# PSU_Schematic.net
KiCad netlist of a schematic drawn in Altium Designer
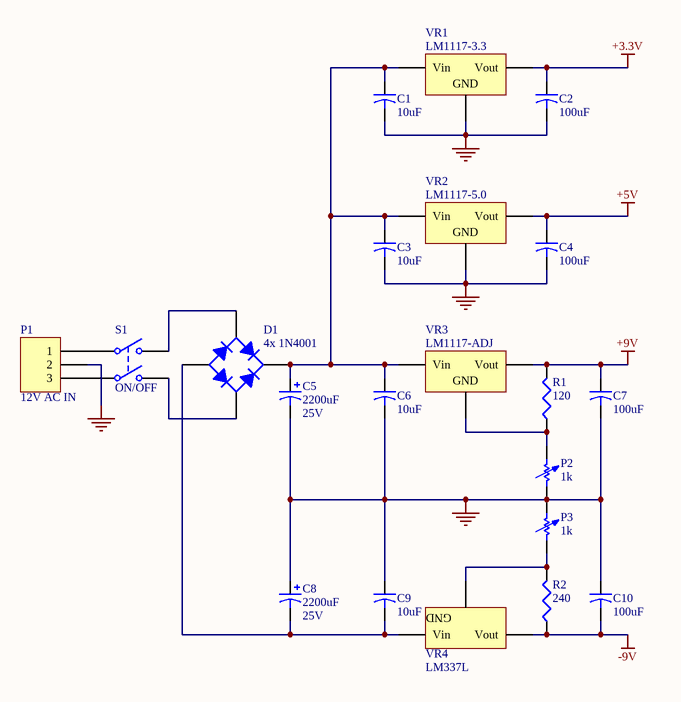
[diagram p0: PSU.Schematic.SchDoc]

(export (version "E")
  (design (tool "Eeschema 10.0.6"))
  (components
    (comp (ref "C1")
      (value "10uF")
      (footprint "CAPR5-4X5")
      (description "Capacitor")
      (fields (field (name "PUBLISHER") "Altium Limited"))
      (libsource (lib "Miscellaneous Devices") (part "Cap2"))
    )
    (comp (ref "C2")
      (value "100uF")
      (footprint "CAPR5-4X5")
      (description "Capacitor")
      (fields (field (name "PUBLISHER") "Altium Limited"))
      (libsource (lib "Miscellaneous Devices") (part "Cap2"))
    )
    (comp (ref "C3")
      (value "10uF")
      (footprint "CAPR5-4X5")
      (description "Capacitor")
      (fields (field (name "PUBLISHER") "Altium Limited"))
      (libsource (lib "Miscellaneous Devices") (part "Cap2"))
    )
    (comp (ref "C4")
      (value "100uF")
      (footprint "CAPR5-4X5")
      (description "Capacitor")
      (fields (field (name "PUBLISHER") "Altium Limited"))
      (libsource (lib "Miscellaneous Devices") (part "Cap2"))
    )
    (comp (ref "C5")
      (value "2200uF")
      (footprint "RB7.6-15")
      (description "Polarized Capacitor (Radial)")
      (fields (field (name "ALTIUM_VALUE") "25V") (field (name "PUBLISHER") "Altium Limited"))
      (libsource (lib "Miscellaneous Devices") (part "Cap Pol1"))
    )
    (comp (ref "C6")
      (value "10uF")
      (footprint "CAPR5-4X5")
      (description "Capacitor")
      (fields (field (name "PUBLISHER") "Altium Limited"))
      (libsource (lib "Miscellaneous Devices") (part "Cap2"))
    )
    (comp (ref "C7")
      (value "100uF")
      (footprint "CAPR5-4X5")
      (description "Capacitor")
      (fields (field (name "PUBLISHER") "Altium Limited"))
      (libsource (lib "Miscellaneous Devices") (part "Cap2"))
    )
    (comp (ref "C8")
      (value "2200uF")
      (footprint "RB7.6-15")
      (description "Polarized Capacitor (Radial)")
      (fields (field (name "ALTIUM_VALUE") "25V") (field (name "PUBLISHER") "Altium Limited"))
      (libsource (lib "Miscellaneous Devices") (part "Cap Pol1"))
    )
    (comp (ref "C9")
      (value "10uF")
      (footprint "CAPR5-4X5")
      (description "Capacitor")
      (fields (field (name "PUBLISHER") "Altium Limited"))
      (libsource (lib "Miscellaneous Devices") (part "Cap2"))
    )
    (comp (ref "C10")
      (value "100uF")
      (footprint "CAPR5-4X5")
      (description "Capacitor")
      (fields (field (name "PUBLISHER") "Altium Limited"))
      (libsource (lib "Miscellaneous Devices") (part "Cap2"))
    )
    (comp (ref "D1")
      (value "4x 1N4001")
      (footprint "D-38")
      (description "Full Wave Diode Bridge")
      (fields (field (name "PUBLISHER") "Altium Limited"))
      (libsource (lib "Miscellaneous Devices") (part "Bridge1"))
    )
    (comp (ref "P1")
      (value "12V AC IN")
      (footprint "HDR1X3")
      (description "Header, 3-Pin")
      (fields (field (name "PUBLISHER") "Altium Limited"))
      (libsource (lib "Miscellaneous Connectors") (part "Header 3"))
    )
    (comp (ref "P2")
      (value "1k")
      (footprint "AXIAL-0.7")
      (description "Variable Resistor")
      (fields (field (name "PUBLISHER") "Altium Limited"))
      (libsource (lib "Miscellaneous Devices") (part "Res Adj1"))
    )
    (comp (ref "P3")
      (value "1k")
      (footprint "AXIAL-0.7")
      (description "Variable Resistor")
      (fields (field (name "PUBLISHER") "Altium Limited"))
      (libsource (lib "Miscellaneous Devices") (part "Res Adj1"))
    )
    (comp (ref "R1")
      (value "120")
      (footprint "J1-0603")
      (description "Resistor")
      (fields (field (name "PUBLISHER") "Altium Limited"))
      (libsource (lib "Miscellaneous Devices") (part "Res3"))
    )
    (comp (ref "R2")
      (value "240")
      (footprint "J1-0603")
      (description "Resistor")
      (fields (field (name "PUBLISHER") "Altium Limited"))
      (libsource (lib "Miscellaneous Devices") (part "Res3"))
    )
    (comp (ref "S1")
      (value "ON/OFF")
      (footprint "DPST-4")
      (description "Double-Pole, Single-Throw Switch")
      (fields (field (name "PUBLISHER") "Altium Limited"))
      (libsource (lib "Miscellaneous Devices") (part "SW-DPST"))
    )
    (comp (ref "VR1")
      (value "LM1117-3.3")
      (footprint "D2PAK_N")
      (description "Voltage Regulator")
      (fields (field (name "PUBLISHER") "Altium Limited"))
      (libsource (lib "") (part "Volt Reg_1"))
    )
    (comp (ref "VR2")
      (value "LM1117-5.0")
      (footprint "D2PAK_N")
      (description "Voltage Regulator")
      (fields (field (name "PUBLISHER") "Altium Limited"))
      (libsource (lib "") (part "Volt Reg_1"))
    )
    (comp (ref "VR3")
      (value "LM1117-ADJ")
      (footprint "D2PAK_N")
      (description "Voltage Regulator")
      (fields (field (name "PUBLISHER") "Altium Limited"))
      (libsource (lib "") (part "Volt Reg_1"))
    )
    (comp (ref "VR4")
      (value "LM337L")
      (footprint "D2PAK_N")
      (description "Voltage Regulator")
      (fields (field (name "PUBLISHER") "Altium Limited"))
      (libsource (lib "Miscellaneous Devices") (part "Volt Reg"))
    )
  )
  (nets
    (net (code "1") (name "+3.3V") (class "Default")
      (node (ref "C2") (pin "1") (pinfunction "1_1") (pintype "passive"))
      (node (ref "VR1") (pin "3") (pinfunction "Vout_3") (pintype "passive"))
    )
    (net (code "2") (name "+5V") (class "Default")
      (node (ref "C4") (pin "1") (pinfunction "1_1") (pintype "passive"))
      (node (ref "VR2") (pin "3") (pinfunction "Vout_3") (pintype "passive"))
    )
    (net (code "3") (name "+9V") (class "Default")
      (node (ref "C7") (pin "1") (pinfunction "1_1") (pintype "passive"))
      (node (ref "R1") (pin "2") (pinfunction "2_2") (pintype "passive"))
      (node (ref "VR3") (pin "3") (pinfunction "Vout_3") (pintype "passive"))
    )
    (net (code "4") (name "-9V") (class "Default")
      (node (ref "C10") (pin "2") (pinfunction "2_2") (pintype "passive"))
      (node (ref "R2") (pin "1") (pinfunction "1_1") (pintype "passive"))
      (node (ref "VR4") (pin "3") (pinfunction "Vout_3") (pintype "passive"))
    )
    (net (code "5") (name "GND") (class "Default")
      (node (ref "C1") (pin "2") (pinfunction "2_2") (pintype "passive"))
      (node (ref "C10") (pin "1") (pinfunction "1_1") (pintype "passive"))
      (node (ref "C2") (pin "2") (pinfunction "2_2") (pintype "passive"))
      (node (ref "C3") (pin "2") (pinfunction "2_2") (pintype "passive"))
      (node (ref "C4") (pin "2") (pinfunction "2_2") (pintype "passive"))
      (node (ref "C5") (pin "2") (pinfunction "2_2") (pintype "passive"))
      (node (ref "C6") (pin "2") (pinfunction "2_2") (pintype "passive"))
      (node (ref "C7") (pin "2") (pinfunction "2_2") (pintype "passive"))
      (node (ref "C8") (pin "1") (pinfunction "1_1") (pintype "passive"))
      (node (ref "C9") (pin "1") (pinfunction "1_1") (pintype "passive"))
      (node (ref "P1") (pin "2") (pinfunction "2_2") (pintype "passive"))
      (node (ref "P2") (pin "1") (pinfunction "1_1") (pintype "passive"))
      (node (ref "P3") (pin "2") (pinfunction "2_2") (pintype "passive"))
      (node (ref "VR1") (pin "2") (pinfunction "GND_2") (pintype "passive"))
      (node (ref "VR2") (pin "2") (pinfunction "GND_2") (pintype "passive"))
    )
    (net (code "6") (name "Net-(D1-A)") (class "Default")
      (node (ref "C8") (pin "2") (pinfunction "2_2") (pintype "passive"))
      (node (ref "C9") (pin "2") (pinfunction "2_2") (pintype "passive"))
      (node (ref "D1") (pin "3") (pinfunction "A_3") (pintype "passive"))
      (node (ref "VR4") (pin "1") (pinfunction "Vin_1") (pintype "passive"))
    )
    (net (code "7") (name "Net-(D1-K)") (class "Default")
      (node (ref "C1") (pin "1") (pinfunction "1_1") (pintype "passive"))
      (node (ref "C3") (pin "1") (pinfunction "1_1") (pintype "passive"))
      (node (ref "C5") (pin "1") (pinfunction "1_1") (pintype "passive"))
      (node (ref "C6") (pin "1") (pinfunction "1_1") (pintype "passive"))
      (node (ref "D1") (pin "1") (pinfunction "K_1") (pintype "passive"))
      (node (ref "VR1") (pin "1") (pinfunction "Vin_1") (pintype "passive"))
      (node (ref "VR2") (pin "1") (pinfunction "Vin_1") (pintype "passive"))
      (node (ref "VR3") (pin "1") (pinfunction "Vin_1") (pintype "passive"))
    )
    (net (code "8") (name "Net-(S1-COMMON1)") (class "Default")
      (node (ref "P1") (pin "1") (pinfunction "1_1") (pintype "passive"))
      (node (ref "S1") (pin "1") (pinfunction "COMMON1_1") (pintype "passive"))
    )
    (net (code "9") (name "Net-(S1-COMMON2)") (class "Default")
      (node (ref "P1") (pin "3") (pinfunction "3_3") (pintype "passive"))
      (node (ref "S1") (pin "3") (pinfunction "COMMON2_3") (pintype "passive"))
    )
    (net (code "10") (name "Net-(S1-NO1)") (class "Default")
      (node (ref "D1") (pin "4") (pinfunction "C_4") (pintype "passive"))
      (node (ref "S1") (pin "2") (pinfunction "NO1_2") (pintype "passive"))
    )
    (net (code "11") (name "Net-(S1-NO2)") (class "Default")
      (node (ref "D1") (pin "2") (pinfunction "C_2") (pintype "passive"))
      (node (ref "S1") (pin "4") (pinfunction "NO2_4") (pintype "passive"))
    )
    (net (code "12") (name "Net-(VR3-GND)") (class "Default")
      (node (ref "P2") (pin "2") (pinfunction "2_2") (pintype "passive"))
      (node (ref "R1") (pin "1") (pinfunction "1_1") (pintype "passive"))
      (node (ref "VR3") (pin "2") (pinfunction "GND_2") (pintype "passive"))
    )
    (net (code "13") (name "Net-(VR4-ADJ)") (class "Default")
      (node (ref "P3") (pin "1") (pinfunction "1_1") (pintype "passive"))
      (node (ref "R2") (pin "2") (pinfunction "2_2") (pintype "passive"))
      (node (ref "VR4") (pin "2") (pinfunction "ADJ_2") (pintype "passive"))
    )
  )
)
